# Sheet1.net
KiCad netlist of a schematic drawn in Altium Designer
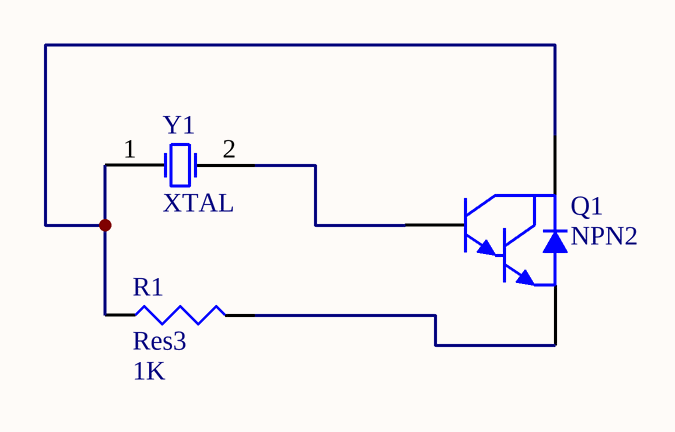
[diagram p0: Sheet1.SchDoc]

(export (version "E")
  (design (tool "Eeschema 10.0.6"))
  (components
    (comp (ref "Q1")
      (value "NPN2")
      (footprint "TO-226-AE")
      (description "NPN Darlington Bipolar Transistor")
      (fields (field (name "PUBLISHER") "Altium Limited"))
      (libsource (lib "Miscellaneous Devices") (part "NPN2"))
    )
    (comp (ref "R1")
      (value "Res3")
      (footprint "J1-0603")
      (description "Resistor")
      (fields (field (name "ALTIUM_VALUE") "1K") (field (name "PUBLISHER") "Altium Limited"))
      (libsource (lib "Miscellaneous Devices") (part "Res3"))
    )
    (comp (ref "Y1")
      (value "XTAL")
      (footprint "R38")
      (description "Crystal Oscillator")
      (fields (field (name "PUBLISHER") "Altium Limited"))
      (libsource (lib "Miscellaneous Devices") (part "XTAL"))
    )
  )
  (nets
    (net (code "1") (name "Net-(Q1-B)") (class "Default")
      (node (ref "Q1") (pin "2") (pinfunction "B_2") (pintype "passive"))
      (node (ref "Y1") (pin "2") (pinfunction "OSC2_2") (pintype "passive"))
    )
    (net (code "2") (name "Net-(Q1-C)") (class "Default")
      (node (ref "Q1") (pin "1") (pinfunction "C_1") (pintype "passive"))
      (node (ref "R1") (pin "1") (pinfunction "1_1") (pintype "passive"))
      (node (ref "Y1") (pin "1") (pinfunction "OSC1_1") (pintype "passive"))
    )
    (net (code "3") (name "Net-(Q1-E)") (class "Default")
      (node (ref "Q1") (pin "3") (pinfunction "E_3") (pintype "passive"))
      (node (ref "R1") (pin "2") (pinfunction "2_2") (pintype "passive"))
    )
  )
)
